# 01-CM4_Conn.net
KiCad netlist of a schematic drawn in Altium Designer
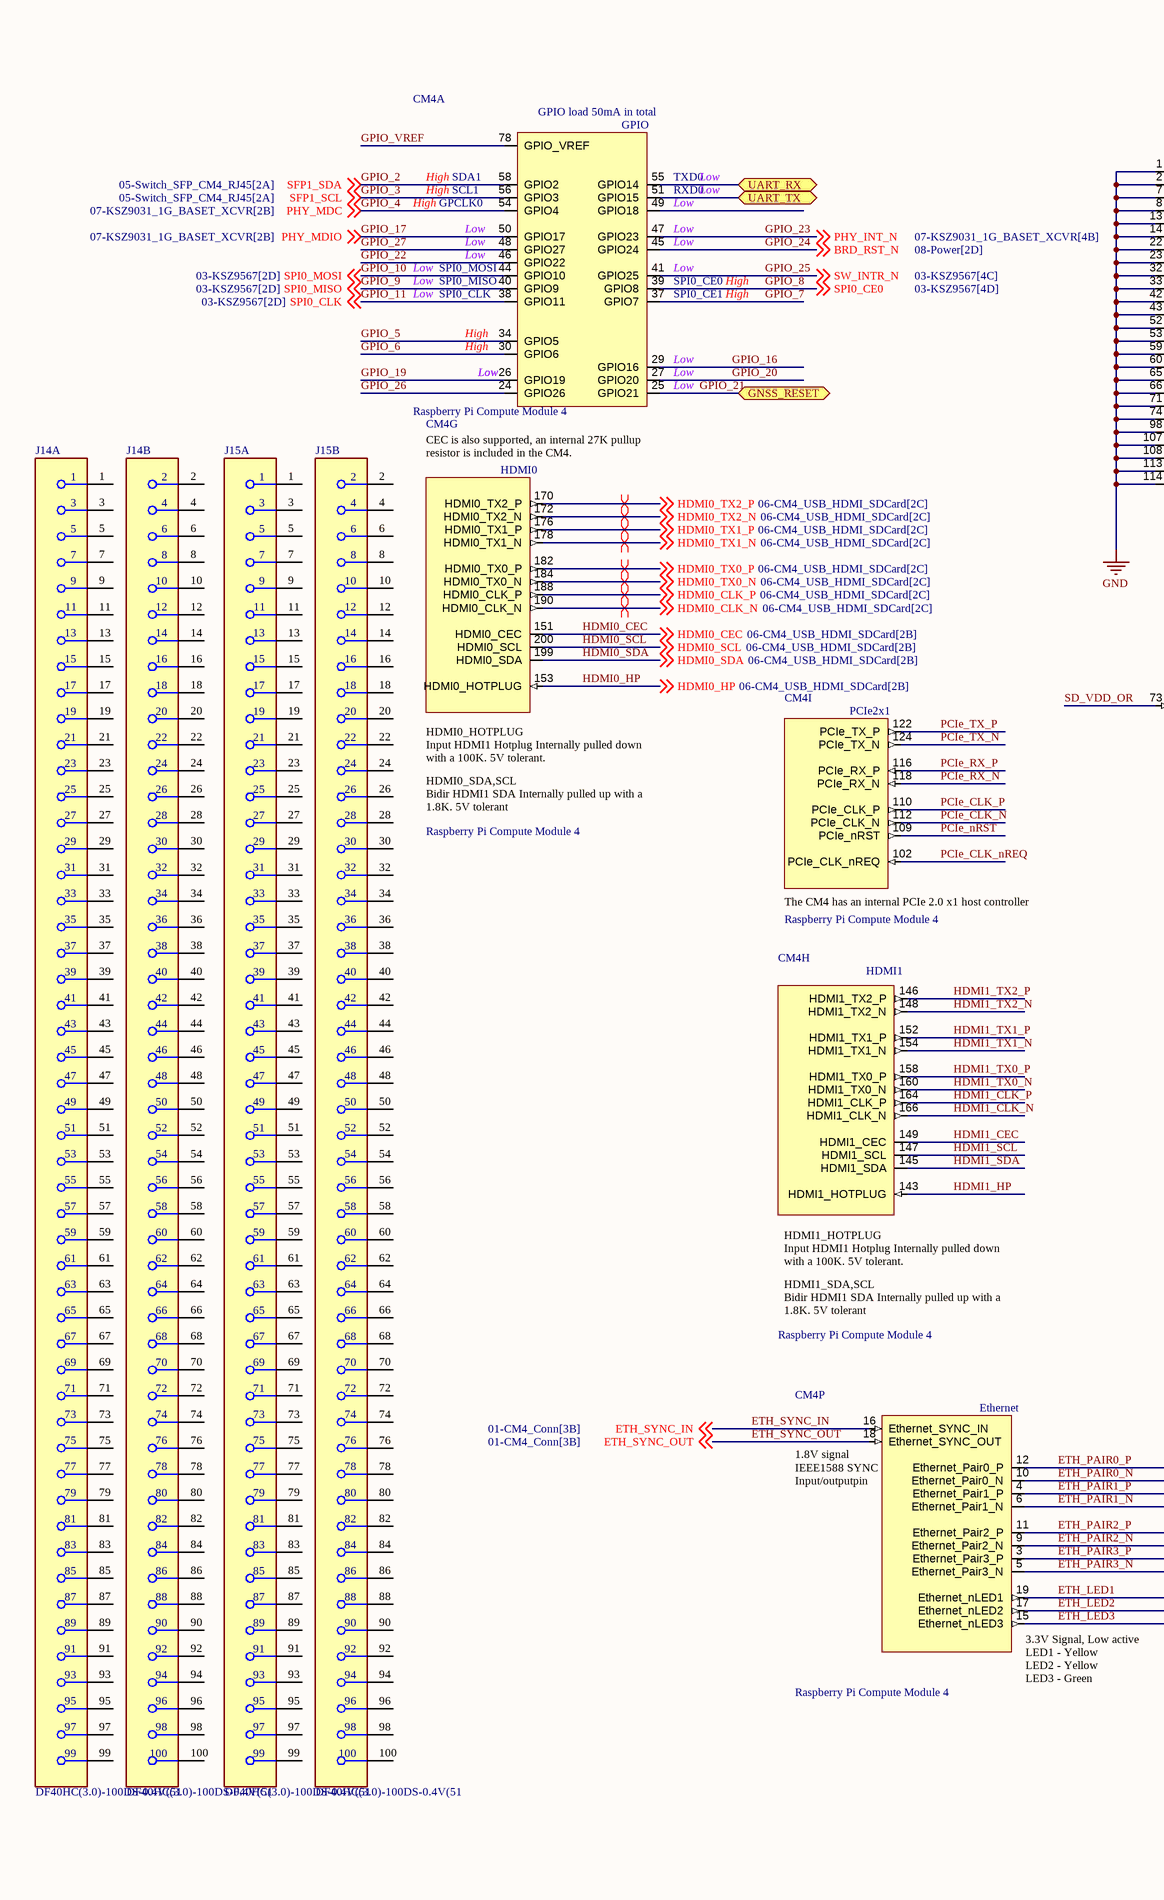
[diagram p0: 01-CM4_Conn.SchDoc, left]
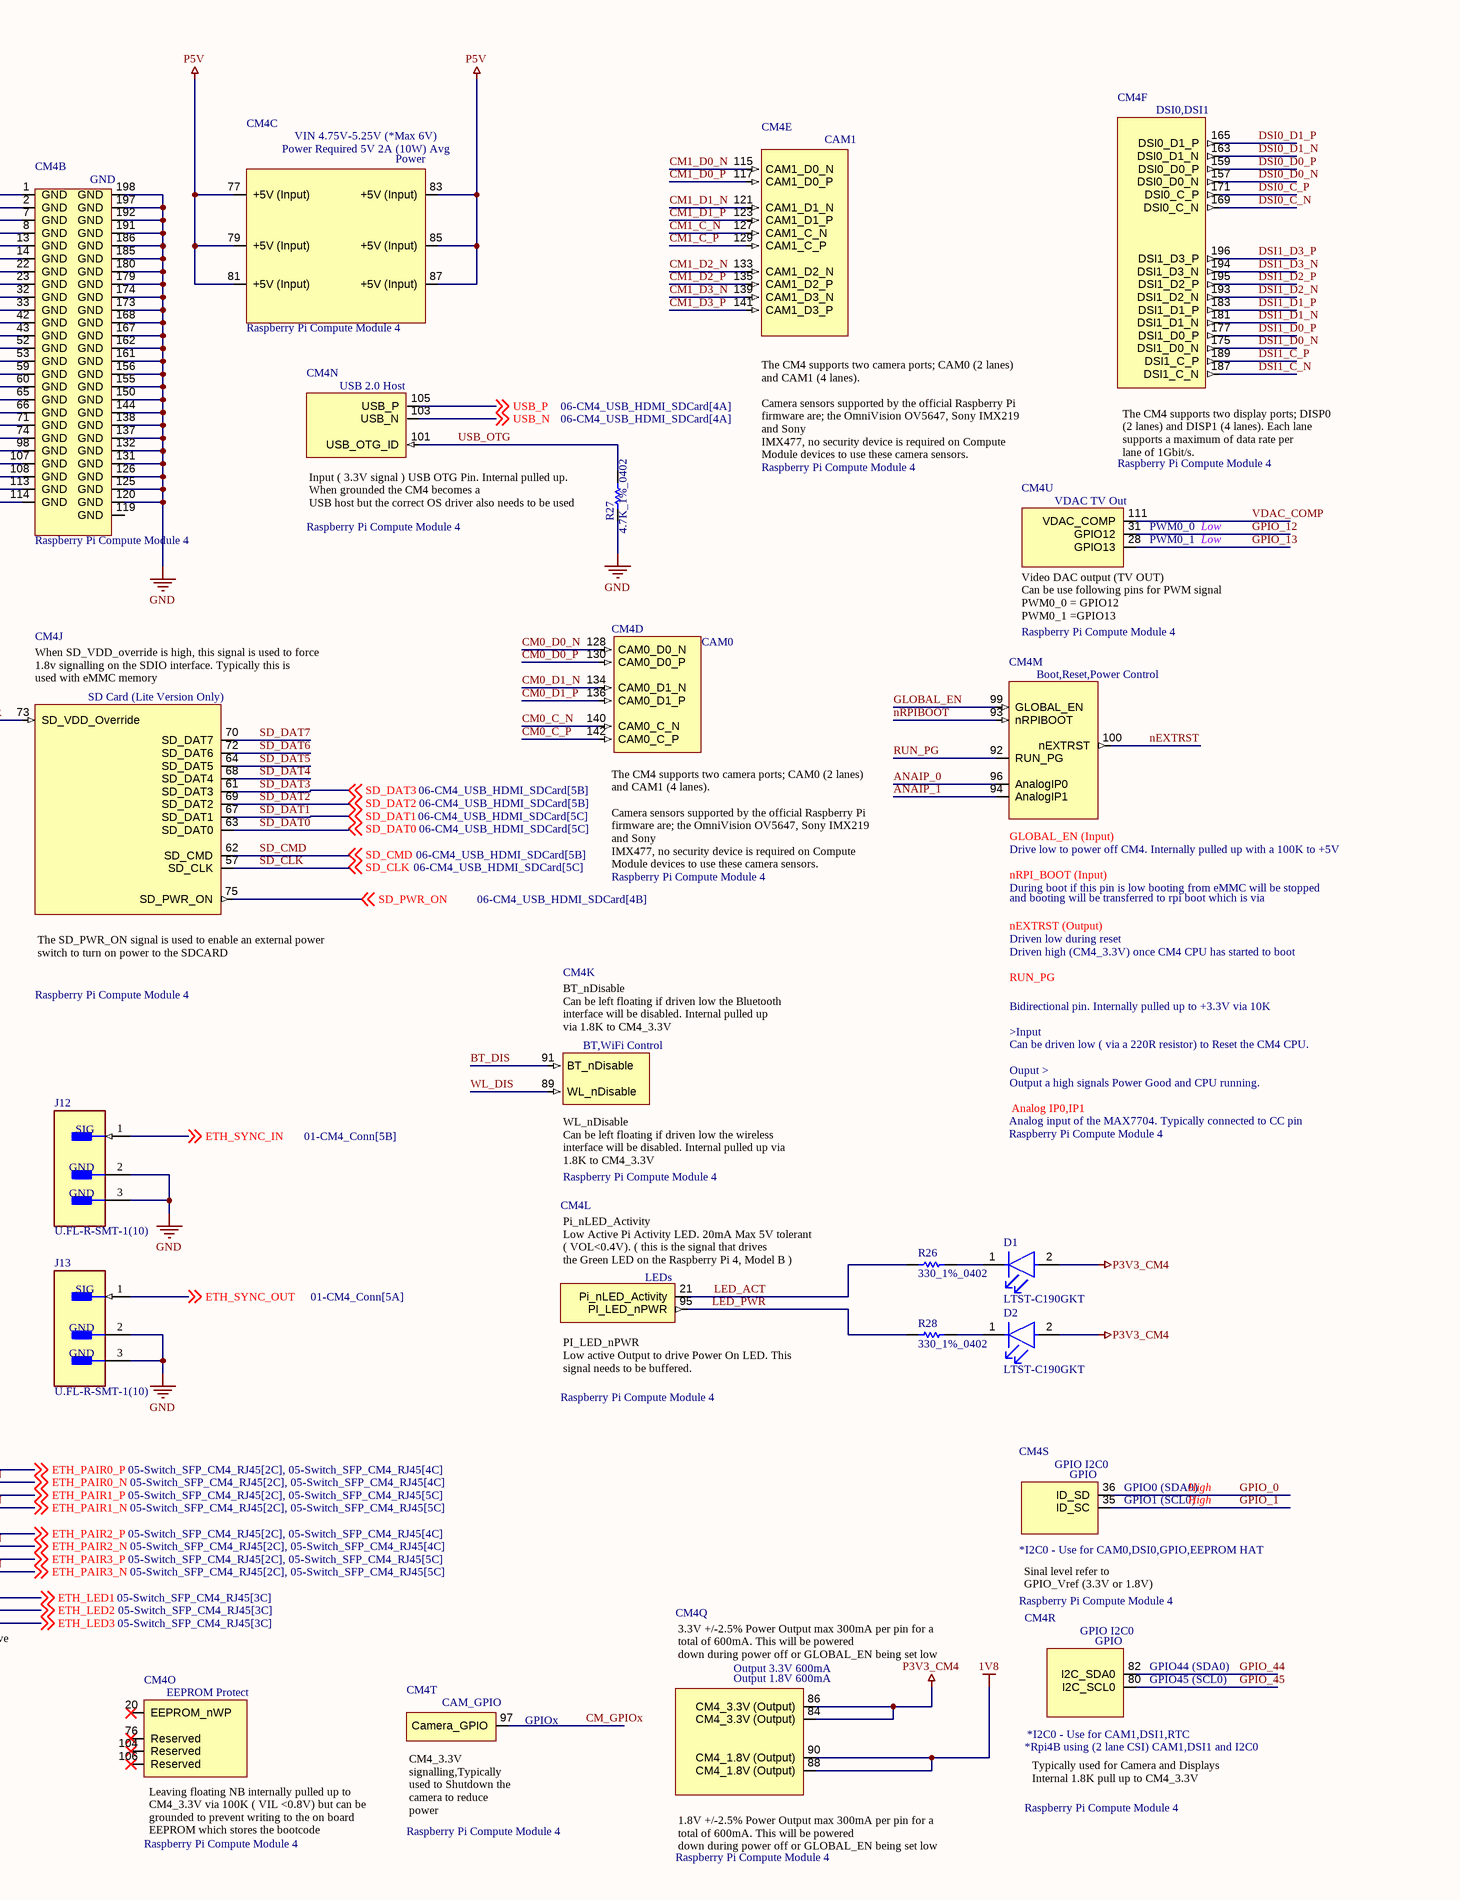
[diagram p1: 01-CM4_Conn.SchDoc, right]

(export (version "E")
  (design (tool "Eeschema 10.0.6"))
  (components
    (comp (ref "CM4")
      (value "Raspberry Pi Compute Module 4")
      (footprint "CM4-F40C-100DS-0.4v_1.5mm_0mm")
      (description "Raspberry Pi Compute Module 4 by Amornthep Phunsin")
      (libsource (lib "CM4") (part "CM4"))
    )
    (comp (ref "D1")
      (value "LTST-C190GKT")
      (footprint "FP-LTST-C190GKT-MFG")
      (description "LED GREEN CLEAR CHIP SMD")
      (fields (field (name "VOLTAGE") "2V"))
      (libsource (lib "Altium Content Vault") (part "8706943c75ba83719d021d2fdc84c58"))
    )
    (comp (ref "D2")
      (value "LTST-C190GKT")
      (footprint "FP-LTST-C190GKT-MFG")
      (description "LED GREEN CLEAR CHIP SMD")
      (fields (field (name "VOLTAGE") "2V"))
      (libsource (lib "Altium Content Vault") (part "8706943c75ba83719d021d2fdc84c58"))
    )
    (comp (ref "J12")
      (value "U.FL-R-SMT-1(10)")
      (footprint "FP-U_FL-R-SMT-1_10-MFG")
      (description "CONN U.FL RCPT STR 50 OHM SMD")
      (libsource (lib "Altium Content Vault") (part "7158abf7d987fa84906f6fb0d115710"))
    )
    (comp (ref "J13")
      (value "U.FL-R-SMT-1(10)")
      (footprint "FP-U_FL-R-SMT-1_10-MFG")
      (description "CONN U.FL RCPT STR 50 OHM SMD")
      (libsource (lib "Altium Content Vault") (part "7158abf7d987fa84906f6fb0d115710"))
    )
    (comp (ref "J14")
      (value "DF40HC(3.0)-100DS-0.4V(51")
      (footprint "FP-DF40HC_3_0_-100DS-0_4V-MFG")
      (description "CONN RCPT 100POS SMD GOLD")
      (libsource (lib "Altium Content Vault") (part "fa457dfecf3ebaea1b28843c89f182e"))
    )
    (comp (ref "J15")
      (value "DF40HC(3.0)-100DS-0.4V(51")
      (footprint "FP-DF40HC_3_0_-100DS-0_4V-MFG")
      (description "CONN RCPT 100POS SMD GOLD")
      (libsource (lib "Altium Content Vault") (part "fa457dfecf3ebaea1b28843c89f182e"))
    )
    (comp (ref "R26")
      (value "330_1%_0402")
      (footprint "RESC1005X40X25NL10T10")
      (fields (field (name "MANUFACTURER") "Panasonic") (field (name "PART NUMBER") "ERA-2AED331X"))
      (libsource (lib "Altium Content Vault") (part "RES"))
    )
    (comp (ref "R27")
      (value "4.7K_1%_0402")
      (footprint "RESC1005X40X25NL10T10")
      (fields (field (name "MANUFACTURER") "Bourns") (field (name "PART NUMBER") "CR0402-FX-4701GLF"))
      (libsource (lib "Altium Content Vault") (part "RES"))
    )
    (comp (ref "R28")
      (value "330_1%_0402")
      (footprint "RESC1005X40X25NL10T10")
      (fields (field (name "MANUFACTURER") "Panasonic") (field (name "PART NUMBER") "ERA-2AED331X"))
      (libsource (lib "Altium Content Vault") (part "RES"))
    )
  )
  (nets
    (net (code "1") (name "/ANAIP_0") (class "Default")
      (node (ref "CM4") (pin "96") (pinfunction "AnalogIP0_96") (pintype "passive"))
    )
    (net (code "2") (name "/ANAIP_1") (class "Default")
      (node (ref "CM4") (pin "94") (pinfunction "AnalogIP1_94") (pintype "passive"))
    )
    (net (code "3") (name "/BT_DIS") (class "Default")
      (node (ref "CM4") (pin "91") (pinfunction "BT_nDisable_91") (pintype "input"))
    )
    (net (code "4") (name "/CM0_C_N") (class "Default")
      (node (ref "CM4") (pin "140") (pinfunction "CAM0_C_N_140") (pintype "input"))
    )
    (net (code "5") (name "/CM0_C_P") (class "Default")
      (node (ref "CM4") (pin "142") (pinfunction "CAM0_C_P_142") (pintype "input"))
    )
    (net (code "6") (name "/CM0_D0_N") (class "Default")
      (node (ref "CM4") (pin "128") (pinfunction "CAM0_D0_N_128") (pintype "input"))
    )
    (net (code "7") (name "/CM0_D0_P") (class "Default")
      (node (ref "CM4") (pin "130") (pinfunction "CAM0_D0_P_130") (pintype "input"))
    )
    (net (code "8") (name "/CM0_D1_N") (class "Default")
      (node (ref "CM4") (pin "134") (pinfunction "CAM0_D1_N_134") (pintype "input"))
    )
    (net (code "9") (name "/CM0_D1_P") (class "Default")
      (node (ref "CM4") (pin "136") (pinfunction "CAM0_D1_P_136") (pintype "input"))
    )
    (net (code "10") (name "/CM1_C_N") (class "Default")
      (node (ref "CM4") (pin "127") (pinfunction "CAM1_C_N_127") (pintype "input"))
    )
    (net (code "11") (name "/CM1_C_P") (class "Default")
      (node (ref "CM4") (pin "129") (pinfunction "CAM1_C_P_129") (pintype "input"))
    )
    (net (code "12") (name "/CM1_D0_N") (class "Default")
      (node (ref "CM4") (pin "115") (pinfunction "CAM1_D0_N_115") (pintype "input"))
    )
    (net (code "13") (name "/CM1_D0_P") (class "Default")
      (node (ref "CM4") (pin "117") (pinfunction "CAM1_D0_P_117") (pintype "input"))
    )
    (net (code "14") (name "/CM1_D1_N") (class "Default")
      (node (ref "CM4") (pin "121") (pinfunction "CAM1_D1_N_121") (pintype "input"))
    )
    (net (code "15") (name "/CM1_D1_P") (class "Default")
      (node (ref "CM4") (pin "123") (pinfunction "CAM1_D1_P_123") (pintype "input"))
    )
    (net (code "16") (name "/CM1_D2_N") (class "Default")
      (node (ref "CM4") (pin "133") (pinfunction "CAM1_D2_N_133") (pintype "input"))
    )
    (net (code "17") (name "/CM1_D2_P") (class "Default")
      (node (ref "CM4") (pin "135") (pinfunction "CAM1_D2_P_135") (pintype "input"))
    )
    (net (code "18") (name "/CM1_D3_N") (class "Default")
      (node (ref "CM4") (pin "139") (pinfunction "CAM1_D3_N_139") (pintype "input"))
    )
    (net (code "19") (name "/CM1_D3_P") (class "Default")
      (node (ref "CM4") (pin "141") (pinfunction "CAM1_D3_P_141") (pintype "input"))
    )
    (net (code "20") (name "/CM_GPIOx") (class "Default")
      (node (ref "CM4") (pin "97") (pinfunction "Camera_GPIO_97") (pintype "passive"))
    )
    (net (code "21") (name "/DSI0_C_N") (class "Default")
      (node (ref "CM4") (pin "169") (pinfunction "DSI0_C_N_169") (pintype "output"))
    )
    (net (code "22") (name "/DSI0_C_P") (class "Default")
      (node (ref "CM4") (pin "171") (pinfunction "DSI0_C_P_171") (pintype "output"))
    )
    (net (code "23") (name "/DSI0_D0_N") (class "Default")
      (node (ref "CM4") (pin "157") (pinfunction "DSI0_D0_N_157") (pintype "output"))
    )
    (net (code "24") (name "/DSI0_D0_P") (class "Default")
      (node (ref "CM4") (pin "159") (pinfunction "DSI0_D0_P_159") (pintype "output"))
    )
    (net (code "25") (name "/DSI0_D1_N") (class "Default")
      (node (ref "CM4") (pin "163") (pinfunction "DSI0_D1_N_163") (pintype "output"))
    )
    (net (code "26") (name "/DSI0_D1_P") (class "Default")
      (node (ref "CM4") (pin "165") (pinfunction "DSI0_D1_P_165") (pintype "output"))
    )
    (net (code "27") (name "/DSI1_C_N") (class "Default")
      (node (ref "CM4") (pin "187") (pinfunction "DSI1_C_N_187") (pintype "output"))
    )
    (net (code "28") (name "/DSI1_C_P") (class "Default")
      (node (ref "CM4") (pin "189") (pinfunction "DSI1_C_P_189") (pintype "output"))
    )
    (net (code "29") (name "/DSI1_D0_N") (class "Default")
      (node (ref "CM4") (pin "175") (pinfunction "DSI1_D0_N_175") (pintype "output"))
    )
    (net (code "30") (name "/DSI1_D0_P") (class "Default")
      (node (ref "CM4") (pin "177") (pinfunction "DSI1_D0_P_177") (pintype "output"))
    )
    (net (code "31") (name "/DSI1_D1_N") (class "Default")
      (node (ref "CM4") (pin "181") (pinfunction "DSI1_D1_N_181") (pintype "output"))
    )
    (net (code "32") (name "/DSI1_D1_P") (class "Default")
      (node (ref "CM4") (pin "183") (pinfunction "DSI1_D1_P_183") (pintype "output"))
    )
    (net (code "33") (name "/DSI1_D2_N") (class "Default")
      (node (ref "CM4") (pin "193") (pinfunction "DSI1_D2_N_193") (pintype "output"))
    )
    (net (code "34") (name "/DSI1_D2_P") (class "Default")
      (node (ref "CM4") (pin "195") (pinfunction "DSI1_D2_P_195") (pintype "output"))
    )
    (net (code "35") (name "/DSI1_D3_N") (class "Default")
      (node (ref "CM4") (pin "194") (pinfunction "DSI1_D3_N_194") (pintype "output"))
    )
    (net (code "36") (name "/DSI1_D3_P") (class "Default")
      (node (ref "CM4") (pin "196") (pinfunction "DSI1_D3_P_196") (pintype "output"))
    )
    (net (code "37") (name "/GLOBAL_EN") (class "Default")
      (node (ref "CM4") (pin "99") (pinfunction "GLOBAL_EN_99") (pintype "input"))
    )
    (net (code "38") (name "/GPIO_0") (class "Default")
      (node (ref "CM4") (pin "36") (pinfunction "ID_SD_36") (pintype "passive"))
    )
    (net (code "39") (name "/GPIO_1") (class "Default")
      (node (ref "CM4") (pin "35") (pinfunction "ID_SC_35") (pintype "passive"))
    )
    (net (code "40") (name "/GPIO_5") (class "Default")
      (node (ref "CM4") (pin "34") (pinfunction "GPIO5_34") (pintype "passive"))
    )
    (net (code "41") (name "/GPIO_6") (class "Default")
      (node (ref "CM4") (pin "30") (pinfunction "GPIO6_30") (pintype "passive"))
    )
    (net (code "42") (name "/GPIO_7") (class "Default")
      (node (ref "CM4") (pin "37") (pinfunction "GPIO7_37") (pintype "passive"))
    )
    (net (code "43") (name "/GPIO_12") (class "Default")
      (node (ref "CM4") (pin "31") (pinfunction "GPIO12_31") (pintype "passive"))
    )
    (net (code "44") (name "/GPIO_13") (class "Default")
      (node (ref "CM4") (pin "28") (pinfunction "GPIO13_28") (pintype "passive"))
    )
    (net (code "45") (name "/GPIO_16") (class "Default")
      (node (ref "CM4") (pin "29") (pinfunction "GPIO16_29") (pintype "passive"))
    )
    (net (code "46") (name "/GPIO_19") (class "Default")
      (node (ref "CM4") (pin "26") (pinfunction "GPIO19_26") (pintype "passive"))
    )
    (net (code "47") (name "/GPIO_20") (class "Default")
      (node (ref "CM4") (pin "27") (pinfunction "GPIO20_27") (pintype "passive"))
    )
    (net (code "48") (name "/GPIO_21") (class "Default")
      (node (ref "CM4") (pin "25") (pinfunction "GPIO21_25") (pintype "passive"))
    )
    (net (code "49") (name "/GPIO_22") (class "Default")
      (node (ref "CM4") (pin "46") (pinfunction "GPIO22_46") (pintype "passive"))
    )
    (net (code "50") (name "/GPIO_26") (class "Default")
      (node (ref "CM4") (pin "24") (pinfunction "GPIO26_24") (pintype "passive"))
    )
    (net (code "51") (name "/GPIO_27") (class "Default")
      (node (ref "CM4") (pin "48") (pinfunction "GPIO27_48") (pintype "passive"))
    )
    (net (code "52") (name "/GPIO_44") (class "Default")
      (node (ref "CM4") (pin "82") (pinfunction "I2C_SDA0_82") (pintype "passive"))
    )
    (net (code "53") (name "/GPIO_45") (class "Default")
      (node (ref "CM4") (pin "80") (pinfunction "I2C_SCL0_80") (pintype "passive"))
    )
    (net (code "54") (name "/GPIO_VREF") (class "Default")
      (node (ref "CM4") (pin "78") (pinfunction "GPIO_VREF_78") (pintype "power_in"))
    )
    (net (code "55") (name "/HDMI1_CEC") (class "Default")
      (node (ref "CM4") (pin "149") (pinfunction "HDMI1_CEC_149") (pintype "open_collector"))
    )
    (net (code "56") (name "/HDMI1_CLK_N") (class "Default")
      (node (ref "CM4") (pin "166") (pinfunction "HDMI1_CLK_N_166") (pintype "output"))
    )
    (net (code "57") (name "/HDMI1_CLK_P") (class "Default")
      (node (ref "CM4") (pin "164") (pinfunction "HDMI1_CLK_P_164") (pintype "output"))
    )
    (net (code "58") (name "/HDMI1_HP") (class "Default")
      (node (ref "CM4") (pin "143") (pinfunction "HDMI1_HOTPLUG_143") (pintype "input"))
    )
    (net (code "59") (name "/HDMI1_SCL") (class "Default")
      (node (ref "CM4") (pin "147") (pinfunction "HDMI1_SCL_147") (pintype "open_collector"))
    )
    (net (code "60") (name "/HDMI1_SDA") (class "Default")
      (node (ref "CM4") (pin "145") (pinfunction "HDMI1_SDA_145") (pintype "bidirectional"))
    )
    (net (code "61") (name "/HDMI1_TX0_N") (class "Default")
      (node (ref "CM4") (pin "160") (pinfunction "HDMI1_TX0_N_160") (pintype "output"))
    )
    (net (code "62") (name "/HDMI1_TX0_P") (class "Default")
      (node (ref "CM4") (pin "158") (pinfunction "HDMI1_TX0_P_158") (pintype "output"))
    )
    (net (code "63") (name "/HDMI1_TX1_N") (class "Default")
      (node (ref "CM4") (pin "154") (pinfunction "HDMI1_TX1_N_154") (pintype "output"))
    )
    (net (code "64") (name "/HDMI1_TX1_P") (class "Default")
      (node (ref "CM4") (pin "152") (pinfunction "HDMI1_TX1_P_152") (pintype "output"))
    )
    (net (code "65") (name "/HDMI1_TX2_N") (class "Default")
      (node (ref "CM4") (pin "148") (pinfunction "HDMI1_TX2_N_148") (pintype "output"))
    )
    (net (code "66") (name "/HDMI1_TX2_P") (class "Default")
      (node (ref "CM4") (pin "146") (pinfunction "HDMI1_TX2_P_146") (pintype "output"))
    )
    (net (code "67") (name "/LED_ACT") (class "Default")
      (node (ref "CM4") (pin "21") (pinfunction "Pi_nLED_Activity_21") (pintype "open_collector"))
      (node (ref "R26") (pin "1") (pinfunction "1_1") (pintype "passive"))
    )
    (net (code "68") (name "/LED_PWR") (class "Default")
      (node (ref "CM4") (pin "95") (pinfunction "PI_LED_nPWR_95") (pintype "output"))
      (node (ref "R28") (pin "1") (pinfunction "1_1") (pintype "passive"))
    )
    (net (code "69") (name "/PCIe_CLK_N") (class "Default")
      (node (ref "CM4") (pin "112") (pinfunction "PCIe_CLK_N_112") (pintype "output"))
    )
    (net (code "70") (name "/PCIe_CLK_P") (class "Default")
      (node (ref "CM4") (pin "110") (pinfunction "PCIe_CLK_P_110") (pintype "output"))
    )
    (net (code "71") (name "/PCIe_CLK_nREQ") (class "Default")
      (node (ref "CM4") (pin "102") (pinfunction "PCIe_CLK_nREQ_102") (pintype "input"))
    )
    (net (code "72") (name "/PCIe_RX_N") (class "Default")
      (node (ref "CM4") (pin "118") (pinfunction "PCIe_RX_N_118") (pintype "input"))
    )
    (net (code "73") (name "/PCIe_RX_P") (class "Default")
      (node (ref "CM4") (pin "116") (pinfunction "PCIe_RX_P_116") (pintype "input"))
    )
    (net (code "74") (name "/PCIe_TX_N") (class "Default")
      (node (ref "CM4") (pin "124") (pinfunction "PCIe_TX_N_124") (pintype "output"))
    )
    (net (code "75") (name "/PCIe_TX_P") (class "Default")
      (node (ref "CM4") (pin "122") (pinfunction "PCIe_TX_P_122") (pintype "output"))
    )
    (net (code "76") (name "/PCIe_nRST") (class "Default")
      (node (ref "CM4") (pin "109") (pinfunction "PCIe_nRST_109") (pintype "output"))
    )
    (net (code "77") (name "/RUN_PG") (class "Default")
      (node (ref "CM4") (pin "92") (pinfunction "RUN_PG_92") (pintype "passive"))
    )
    (net (code "78") (name "/SD_DAT4") (class "Default")
      (node (ref "CM4") (pin "68") (pinfunction "SD_DAT4_68") (pintype "passive"))
    )
    (net (code "79") (name "/SD_DAT5") (class "Default")
      (node (ref "CM4") (pin "64") (pinfunction "SD_DAT5_64") (pintype "passive"))
    )
    (net (code "80") (name "/SD_DAT6") (class "Default")
      (node (ref "CM4") (pin "72") (pinfunction "SD_DAT6_72") (pintype "passive"))
    )
    (net (code "81") (name "/SD_DAT7") (class "Default")
      (node (ref "CM4") (pin "70") (pinfunction "SD_DAT7_70") (pintype "passive"))
    )
    (net (code "82") (name "/SD_VDD_OR") (class "Default")
      (node (ref "CM4") (pin "73") (pinfunction "SD_VDD_Override_73") (pintype "input"))
    )
    (net (code "83") (name "/UART_RX") (class "Default")
      (node (ref "CM4") (pin "55") (pinfunction "GPIO14_55") (pintype "passive"))
    )
    (net (code "84") (name "/UART_TX") (class "Default")
      (node (ref "CM4") (pin "51") (pinfunction "GPIO15_51") (pintype "passive"))
    )
    (net (code "85") (name "/USB_OTG") (class "Default")
      (node (ref "CM4") (pin "101") (pinfunction "USB_OTG_ID_101") (pintype "input"))
      (node (ref "R27") (pin "1") (pinfunction "1_1") (pintype "passive"))
    )
    (net (code "86") (name "/VDAC_COMP") (class "Default")
      (node (ref "CM4") (pin "111") (pinfunction "VDAC_COMP_111") (pintype "passive"))
    )
    (net (code "87") (name "/WL_DIS") (class "Default")
      (node (ref "CM4") (pin "89") (pinfunction "WL_nDisable_89") (pintype "input"))
    )
    (net (code "88") (name "/nEXTRST") (class "Default")
      (node (ref "CM4") (pin "100") (pinfunction "nEXTRST_100") (pintype "output"))
    )
    (net (code "89") (name "/nRPIBOOT") (class "Default")
      (node (ref "CM4") (pin "93") (pinfunction "nRPIBOOT_93") (pintype "input"))
    )
    (net (code "90") (name "1V8") (class "Default")
      (node (ref "CM4") (pin "88") (pinfunction "CM4_1.8V_(Output)_88") (pintype "power_in"))
      (node (ref "CM4") (pin "90") (pinfunction "CM4_1.8V_(Output)_90") (pintype "power_in"))
    )
    (net (code "91") (name "BRD_RST_N") (class "Default")
      (node (ref "CM4") (pin "45") (pinfunction "GPIO24_45") (pintype "passive"))
    )
    (net (code "92") (name "ETH_LED1") (class "Default")
      (node (ref "CM4") (pin "19") (pinfunction "Ethernet_nLED1_19") (pintype "output"))
    )
    (net (code "93") (name "ETH_LED2") (class "Default")
      (node (ref "CM4") (pin "17") (pinfunction "Ethernet_nLED2_17") (pintype "output"))
    )
    (net (code "94") (name "ETH_LED3") (class "Default")
      (node (ref "CM4") (pin "15") (pinfunction "Ethernet_nLED3_15") (pintype "output"))
    )
    (net (code "95") (name "ETH_PAIR0_N") (class "Default")
      (node (ref "CM4") (pin "10") (pinfunction "Ethernet_Pair0_N_10") (pintype "passive"))
    )
    (net (code "96") (name "ETH_PAIR0_P") (class "Default")
      (node (ref "CM4") (pin "12") (pinfunction "Ethernet_Pair0_P_12") (pintype "passive"))
    )
    (net (code "97") (name "ETH_PAIR1_N") (class "Default")
      (node (ref "CM4") (pin "6") (pinfunction "Ethernet_Pair1_N_6") (pintype "passive"))
    )
    (net (code "98") (name "ETH_PAIR1_P") (class "Default")
      (node (ref "CM4") (pin "4") (pinfunction "Ethernet_Pair1_P_4") (pintype "passive"))
    )
    (net (code "99") (name "ETH_PAIR2_N") (class "Default")
      (node (ref "CM4") (pin "9") (pinfunction "Ethernet_Pair2_N_9") (pintype "passive"))
    )
    (net (code "100") (name "ETH_PAIR2_P") (class "Default")
      (node (ref "CM4") (pin "11") (pinfunction "Ethernet_Pair2_P_11") (pintype "passive"))
    )
    (net (code "101") (name "ETH_PAIR3_N") (class "Default")
      (node (ref "CM4") (pin "5") (pinfunction "Ethernet_Pair3_N_5") (pintype "passive"))
    )
    (net (code "102") (name "ETH_PAIR3_P") (class "Default")
      (node (ref "CM4") (pin "3") (pinfunction "Ethernet_Pair3_P_3") (pintype "passive"))
    )
    (net (code "103") (name "ETH_SYNC_IN") (class "Default")
      (node (ref "CM4") (pin "16") (pinfunction "Ethernet_SYNC_IN_16") (pintype "input"))
      (node (ref "J12") (pin "1") (pinfunction "SIG_1") (pintype "input"))
    )
    (net (code "104") (name "ETH_SYNC_OUT") (class "Default")
      (node (ref "CM4") (pin "18") (pinfunction "Ethernet_SYNC_OUT_18") (pintype "input"))
      (node (ref "J13") (pin "1") (pinfunction "SIG_1") (pintype "input"))
    )
    (net (code "105") (name "GND") (class "Default")
      (node (ref "CM4") (pin "1") (pinfunction "GND_1") (pintype "power_in"))
      (node (ref "CM4") (pin "107") (pinfunction "GND_107") (pintype "power_in"))
      (node (ref "CM4") (pin "108") (pinfunction "GND_108") (pintype "power_in"))
      (node (ref "CM4") (pin "113") (pinfunction "GND_113") (pintype "power_in"))
      (node (ref "CM4") (pin "114") (pinfunction "GND_114") (pintype "power_in"))
      (node (ref "CM4") (pin "120") (pinfunction "GND_120") (pintype "power_in"))
      (node (ref "CM4") (pin "125") (pinfunction "GND_125") (pintype "power_in"))
      (node (ref "CM4") (pin "126") (pinfunction "GND_126") (pintype "power_in"))
      (node (ref "CM4") (pin "13") (pinfunction "GND_13") (pintype "power_in"))
      (node (ref "CM4") (pin "131") (pinfunction "GND_131") (pintype "power_in"))
      (node (ref "CM4") (pin "132") (pinfunction "GND_132") (pintype "power_in"))
      (node (ref "CM4") (pin "137") (pinfunction "GND_137") (pintype "power_in"))
      (node (ref "CM4") (pin "138") (pinfunction "GND_138") (pintype "power_in"))
      (node (ref "CM4") (pin "14") (pinfunction "GND_14") (pintype "power_in"))
      (node (ref "CM4") (pin "144") (pinfunction "GND_144") (pintype "power_in"))
      (node (ref "CM4") (pin "150") (pinfunction "GND_150") (pintype "power_in"))
      (node (ref "CM4") (pin "155") (pinfunction "GND_155") (pintype "power_in"))
      (node (ref "CM4") (pin "156") (pinfunction "GND_156") (pintype "power_in"))
      (node (ref "CM4") (pin "161") (pinfunction "GND_161") (pintype "power_in"))
      (node (ref "CM4") (pin "162") (pinfunction "GND_162") (pintype "power_in"))
      (node (ref "CM4") (pin "167") (pinfunction "GND_167") (pintype "power_in"))
      (node (ref "CM4") (pin "168") (pinfunction "GND_168") (pintype "power_in"))
      (node (ref "CM4") (pin "173") (pinfunction "GND_173") (pintype "power_in"))
      (node (ref "CM4") (pin "174") (pinfunction "GND_174") (pintype "power_in"))
      (node (ref "CM4") (pin "179") (pinfunction "GND_179") (pintype "power_in"))
      (node (ref "CM4") (pin "180") (pinfunction "GND_180") (pintype "power_in"))
      (node (ref "CM4") (pin "185") (pinfunction "GND_185") (pintype "power_in"))
      (node (ref "CM4") (pin "186") (pinfunction "GND_186") (pintype "power_in"))
      (node (ref "CM4") (pin "191") (pinfunction "GND_191") (pintype "power_in"))
      (node (ref "CM4") (pin "192") (pinfunction "GND_192") (pintype "power_in"))
      (node (ref "CM4") (pin "197") (pinfunction "GND_197") (pintype "power_in"))
      (node (ref "CM4") (pin "198") (pinfunction "GND_198") (pintype "power_in"))
      (node (ref "CM4") (pin "2") (pinfunction "GND_2") (pintype "power_in"))
      (node (ref "CM4") (pin "22") (pinfunction "GND_22") (pintype "power_in"))
      (node (ref "CM4") (pin "23") (pinfunction "GND_23") (pintype "power_in"))
      (node (ref "CM4") (pin "32") (pinfunction "GND_32") (pintype "power_in"))
      (node (ref "CM4") (pin "33") (pinfunction "GND_33") (pintype "power_in"))
      (node (ref "CM4") (pin "42") (pinfunction "GND_42") (pintype "power_in"))
      (node (ref "CM4") (pin "43") (pinfunction "GND_43") (pintype "power_in"))
      (node (ref "CM4") (pin "52") (pinfunction "GND_52") (pintype "power_in"))
      (node (ref "CM4") (pin "53") (pinfunction "GND_53") (pintype "power_in"))
      (node (ref "CM4") (pin "59") (pinfunction "GND_59") (pintype "power_in"))
      (node (ref "CM4") (pin "60") (pinfunction "GND_60") (pintype "power_in"))
      (node (ref "CM4") (pin "65") (pinfunction "GND_65") (pintype "power_in"))
      (node (ref "CM4") (pin "66") (pinfunction "GND_66") (pintype "power_in"))
      (node (ref "CM4") (pin "7") (pinfunction "GND_7") (pintype "power_in"))
      (node (ref "CM4") (pin "71") (pinfunction "GND_71") (pintype "power_in"))
      (node (ref "CM4") (pin "74") (pinfunction "GND_74") (pintype "power_in"))
      (node (ref "CM4") (pin "8") (pinfunction "GND_8") (pintype "power_in"))
      (node (ref "CM4") (pin "98") (pinfunction "GND_98") (pintype "power_in"))
      (node (ref "J12") (pin "2") (pinfunction "GND_2") (pintype "power_in"))
      (node (ref "J12") (pin "3") (pinfunction "GND_3") (pintype "power_in"))
      (node (ref "J13") (pin "2") (pinfunction "GND_2") (pintype "power_in"))
      (node (ref "J13") (pin "3") (pinfunction "GND_3") (pintype "power_in"))
      (node (ref "R27") (pin "2") (pinfunction "2_2") (pintype "passive"))
    )
    (net (code "106") (name "HDMI0_CEC") (class "Default")
      (node (ref "CM4") (pin "151") (pinfunction "HDMI0_CEC_151") (pintype "open_collector"))
    )
    (net (code "107") (name "HDMI0_CLK_N") (class "Default")
      (node (ref "CM4") (pin "190") (pinfunction "HDMI0_CLK_N_190") (pintype "output"))
    )
    (net (code "108") (name "HDMI0_CLK_P") (class "Default")
      (node (ref "CM4") (pin "188") (pinfunction "HDMI0_CLK_P_188") (pintype "output"))
    )
    (net (code "109") (name "HDMI0_HP") (class "Default")
      (node (ref "CM4") (pin "153") (pinfunction "HDMI0_HOTPLUG_153") (pintype "input"))
    )
    (net (code "110") (name "HDMI0_SCL") (class "Default")
      (node (ref "CM4") (pin "200") (pinfunction "HDMI0_SCL_200") (pintype "open_collector"))
    )
    (net (code "111") (name "HDMI0_SDA") (class "Default")
      (node (ref "CM4") (pin "199") (pinfunction "HDMI0_SDA_199") (pintype "bidirectional"))
    )
    (net (code "112") (name "HDMI0_TX0_N") (class "Default")
      (node (ref "CM4") (pin "184") (pinfunction "HDMI0_TX0_N_184") (pintype "output"))
    )
    (net (code "113") (name "HDMI0_TX0_P") (class "Default")
      (node (ref "CM4") (pin "182") (pinfunction "HDMI0_TX0_P_182") (pintype "output"))
    )
    (net (code "114") (name "HDMI0_TX1_N") (class "Default")
      (node (ref "CM4") (pin "178") (pinfunction "HDMI0_TX1_N_178") (pintype "output"))
    )
    (net (code "115") (name "HDMI0_TX1_P") (class "Default")
      (node (ref "CM4") (pin "176") (pinfunction "HDMI0_TX1_P_176") (pintype "output"))
    )
    (net (code "116") (name "HDMI0_TX2_N") (class "Default")
      (node (ref "CM4") (pin "172") (pinfunction "HDMI0_TX2_N_172") (pintype "output"))
    )
    (net (code "117") (name "HDMI0_TX2_P") (class "Default")
      (node (ref "CM4") (pin "170") (pinfunction "HDMI0_TX2_P_170") (pintype "output"))
    )
    (net (code "118") (name "Net-(D1-C)") (class "Default")
      (node (ref "D1") (pin "1") (pinfunction "C_1") (pintype "passive"))
      (node (ref "R26") (pin "2") (pinfunction "2_2") (pintype "passive"))
    )
    (net (code "119") (name "Net-(D2-C)") (class "Default")
      (node (ref "D2") (pin "1") (pinfunction "C_1") (pintype "passive"))
      (node (ref "R28") (pin "2") (pinfunction "2_2") (pintype "passive"))
    )
    (net (code "120") (name "P3V3_CM4") (class "Default")
      (node (ref "CM4") (pin "84") (pinfunction "CM4_3.3V_(Output)_84") (pintype "power_in"))
      (node (ref "CM4") (pin "86") (pinfunction "CM4_3.3V_(Output)_86") (pintype "power_in"))
      (node (ref "D1") (pin "2") (pinfunction "A_2") (pintype "passive"))
      (node (ref "D2") (pin "2") (pinfunction "A_2") (pintype "passive"))
    )
    (net (code "121") (name "P5V") (class "Default")
      (node (ref "CM4") (pin "77") (pinfunction "+5V_(Input)_77") (pintype "power_in"))
      (node (ref "CM4") (pin "79") (pinfunction "+5V_(Input)_79") (pintype "power_in"))
      (node (ref "CM4") (pin "81") (pinfunction "+5V_(Input)_81") (pintype "power_in"))
      (node (ref "CM4") (pin "83") (pinfunction "+5V_(Input)_83") (pintype "power_in"))
      (node (ref "CM4") (pin "85") (pinfunction "+5V_(Input)_85") (pintype "power_in"))
      (node (ref "CM4") (pin "87") (pinfunction "+5V_(Input)_87") (pintype "power_in"))
    )
    (net (code "122") (name "PHY_INT_N") (class "Default")
      (node (ref "CM4") (pin "47") (pinfunction "GPIO23_47") (pintype "passive"))
    )
    (net (code "123") (name "PHY_MDC") (class "Default")
      (node (ref "CM4") (pin "54") (pinfunction "GPIO4_54") (pintype "passive"))
    )
    (net (code "124") (name "PHY_MDIO") (class "Default")
      (node (ref "CM4") (pin "50") (pinfunction "GPIO17_50") (pintype "passive"))
    )
    (net (code "125") (name "SD_CLK") (class "Default")
      (node (ref "CM4") (pin "57") (pinfunction "SD_CLK_57") (pintype "passive"))
    )
    (net (code "126") (name "SD_CMD") (class "Default")
      (node (ref "CM4") (pin "62") (pinfunction "SD_CMD_62") (pintype "passive"))
    )
    (net (code "127") (name "SD_DAT0") (class "Default")
      (node (ref "CM4") (pin "63") (pinfunction "SD_DAT0_63") (pintype "passive"))
    )
    (net (code "128") (name "SD_DAT1") (class "Default")
      (node (ref "CM4") (pin "67") (pinfunction "SD_DAT1_67") (pintype "passive"))
    )
    (net (code "129") (name "SD_DAT2") (class "Default")
      (node (ref "CM4") (pin "69") (pinfunction "SD_DAT2_69") (pintype "passive"))
    )
    (net (code "130") (name "SD_DAT3") (class "Default")
      (node (ref "CM4") (pin "61") (pinfunction "SD_DAT3_61") (pintype "passive"))
    )
    (net (code "131") (name "SD_PWR_ON") (class "Default")
      (node (ref "CM4") (pin "75") (pinfunction "SD_PWR_ON_75") (pintype "output"))
    )
    (net (code "132") (name "SFP1_SCL") (class "Default")
      (node (ref "CM4") (pin "56") (pinfunction "GPIO3_56") (pintype "passive"))
    )
    (net (code "133") (name "SFP1_SDA") (class "Default")
      (node (ref "CM4") (pin "58") (pinfunction "GPIO2_58") (pintype "passive"))
    )
    (net (code "134") (name "SPI0_CE0") (class "Default")
      (node (ref "CM4") (pin "39") (pinfunction "GPIO8_39") (pintype "passive"))
    )
    (net (code "135") (name "SPI0_CLK") (class "Default")
      (node (ref "CM4") (pin "38") (pinfunction "GPIO11_38") (pintype "passive"))
    )
    (net (code "136") (name "SPI0_MISO") (class "Default")
      (node (ref "CM4") (pin "40") (pinfunction "GPIO9_40") (pintype "passive"))
    )
    (net (code "137") (name "SPI0_MOSI") (class "Default")
      (node (ref "CM4") (pin "44") (pinfunction "GPIO10_44") (pintype "passive"))
    )
    (net (code "138") (name "SW_INTR_N") (class "Default")
      (node (ref "CM4") (pin "41") (pinfunction "GPIO25_41") (pintype "passive"))
    )
    (net (code "139") (name "USB_N") (class "Default")
      (node (ref "CM4") (pin "103") (pinfunction "USB_N_103") (pintype "passive"))
    )
    (net (code "140") (name "USB_P") (class "Default")
      (node (ref "CM4") (pin "105") (pinfunction "USB_P_105") (pintype "passive"))
    )
    (net (code "141") (name "unconnected-(CM4A-GPIO18-Pad49)") (class "Default")
      (node (ref "CM4") (pin "49") (pinfunction "GPIO18_49") (pintype "passive"))
    )
    (net (code "142") (name "unconnected-(CM4B-GND-Pad119)") (class "Default")
      (node (ref "CM4") (pin "119") (pinfunction "GND_119") (pintype "power_in"))
    )
    (net (code "143") (name "unconnected-(CM4O-EEPROM_nWP-Pad20)") (class "Default")
      (node (ref "CM4") (pin "20") (pinfunction "EEPROM_nWP_20") (pintype "passive+no_connect"))
    )
    (net (code "144") (name "unconnected-(CM4O-Reserved-Pad76)") (class "Default")
      (node (ref "CM4") (pin "76") (pinfunction "Reserved_76") (pintype "passive+no_connect"))
    )
    (net (code "145") (name "unconnected-(CM4O-Reserved-Pad104)") (class "Default")
      (node (ref "CM4") (pin "104") (pinfunction "Reserved_104") (pintype "passive+no_connect"))
    )
    (net (code "146") (name "unconnected-(CM4O-Reserved-Pad106)") (class "Default")
      (node (ref "CM4") (pin "106") (pinfunction "Reserved_106") (pintype "passive+no_connect"))
    )
    (net (code "147") (name "unconnected-(J14-Pad1)") (class "Default")
      (node (ref "J14") (pin "1") (pinfunction "1_1") (pintype "passive"))
    )
    (net (code "148") (name "unconnected-(J14-Pad2)") (class "Default")
      (node (ref "J14") (pin "2") (pinfunction "2_2") (pintype "passive"))
    )
    (net (code "149") (name "unconnected-(J14-Pad3)") (class "Default")
      (node (ref "J14") (pin "3") (pinfunction "3_3") (pintype "passive"))
    )
    (net (code "150") (name "unconnected-(J14-Pad4)") (class "Default")
      (node (ref "J14") (pin "4") (pinfunction "4_4") (pintype "passive"))
    )
    (net (code "151") (name "unconnected-(J14-Pad5)") (class "Default")
      (node (ref "J14") (pin "5") (pinfunction "5_5") (pintype "passive"))
    )
    (net (code "152") (name "unconnected-(J14-Pad6)") (class "Default")
      (node (ref "J14") (pin "6") (pinfunction "6_6") (pintype "passive"))
    )
    (net (code "153") (name "unconnected-(J14-Pad7)") (class "Default")
      (node (ref "J14") (pin "7") (pinfunction "7_7") (pintype "passive"))
    )
    (net (code "154") (name "unconnected-(J14-Pad8)") (class "Default")
      (node (ref "J14") (pin "8") (pinfunction "8_8") (pintype "passive"))
    )
    (net (code "155") (name "unconnected-(J14-Pad9)") (class "Default")
      (node (ref "J14") (pin "9") (pinfunction "9_9") (pintype "passive"))
    )
    (net (code "156") (name "unconnected-(J14-Pad10)") (class "Default")
      (node (ref "J14") (pin "10") (pinfunction "10_10") (pintype "passive"))
    )
    (net (code "157") (name "unconnected-(J14-Pad11)") (class "Default")
      (node (ref "J14") (pin "11") (pinfunction "11_11") (pintype "passive"))
    )
    (net (code "158") (name "unconnected-(J14-Pad12)") (class "Default")
      (node (ref "J14") (pin "12") (pinfunction "12_12") (pintype "passive"))
    )
    (net (code "159") (name "unconnected-(J14-Pad13)") (class "Default")
      (node (ref "J14") (pin "13") (pinfunction "13_13") (pintype "passive"))
    )
    (net (code "160") (name "unconnected-(J14-Pad14)") (class "Default")
      (node (ref "J14") (pin "14") (pinfunction "14_14") (pintype "passive"))
    )
    (net (code "161") (name "unconnected-(J14-Pad15)") (class "Default")
      (node (ref "J14") (pin "15") (pinfunction "15_15") (pintype "passive"))
    )
    (net (code "162") (name "unconnected-(J14-Pad16)") (class "Default")
      (node (ref "J14") (pin "16") (pinfunction "16_16") (pintype "passive"))
    )
    (net (code "163") (name "unconnected-(J14-Pad17)") (class "Default")
      (node (ref "J14") (pin "17") (pinfunction "17_17") (pintype "passive"))
    )
    (net (code "164") (name "unconnected-(J14-Pad18)") (class "Default")
      (node (ref "J14") (pin "18") (pinfunction "18_18") (pintype "passive"))
    )
    (net (code "165") (name "unconnected-(J14-Pad19)") (class "Default")
      (node (ref "J14") (pin "19") (pinfunction "19_19") (pintype "passive"))
    )
    (net (code "166") (name "unconnected-(J14-Pad20)") (class "Default")
      (node (ref "J14") (pin "20") (pinfunction "20_20") (pintype "passive"))
    )
    (net (code "167") (name "unconnected-(J14-Pad21)") (class "Default")
      (node (ref "J14") (pin "21") (pinfunction "21_21") (pintype "passive"))
    )
    (net (code "168") (name "unconnected-(J14-Pad22)") (class "Default")
      (node (ref "J14") (pin "22") (pinfunction "22_22") (pintype "passive"))
    )
    (net (code "169") (name "unconnected-(J14-Pad23)") (class "Default")
      (node (ref "J14") (pin "23") (pinfunction "23_23") (pintype "passive"))
    )
    (net (code "170") (name "unconnected-(J14-Pad24)") (class "Default")
      (node (ref "J14") (pin "24") (pinfunction "24_24") (pintype "passive"))
    )
    (net (code "171") (name "unconnected-(J14-Pad25)") (class "Default")
      (node (ref "J14") (pin "25") (pinfunction "25_25") (pintype "passive"))
    )
    (net (code "172") (name "unconnected-(J14-Pad26)") (class "Default")
      (node (ref "J14") (pin "26") (pinfunction "26_26") (pintype "passive"))
    )
    (net (code "173") (name "unconnected-(J14-Pad27)") (class "Default")
      (node (ref "J14") (pin "27") (pinfunction "27_27") (pintype "passive"))
    )
    (net (code "174") (name "unconnected-(J14-Pad28)") (class "Default")
      (node (ref "J14") (pin "28") (pinfunction "28_28") (pintype "passive"))
    )
    (net (code "175") (name "unconnected-(J14-Pad29)") (class "Default")
      (node (ref "J14") (pin "29") (pinfunction "29_29") (pintype "passive"))
    )
    (net (code "176") (name "unconnected-(J14-Pad30)") (class "Default")
      (node (ref "J14") (pin "30") (pinfunction "30_30") (pintype "passive"))
    )
    (net (code "177") (name "unconnected-(J14-Pad31)") (class "Default")
      (node (ref "J14") (pin "31") (pinfunction "31_31") (pintype "passive"))
    )
    (net (code "178") (name "unconnected-(J14-Pad32)") (class "Default")
      (node (ref "J14") (pin "32") (pinfunction "32_32") (pintype "passive"))
    )
    (net (code "179") (name "unconnected-(J14-Pad33)") (class "Default")
      (node (ref "J14") (pin "33") (pinfunction "33_33") (pintype "passive"))
    )
    (net (code "180") (name "unconnected-(J14-Pad34)") (class "Default")
      (node (ref "J14") (pin "34") (pinfunction "34_34") (pintype "passive"))
    )
    (net (code "181") (name "unconnected-(J14-Pad35)") (class "Default")
      (node (ref "J14") (pin "35") (pinfunction "35_35") (pintype "passive"))
    )
    (net (code "182") (name "unconnected-(J14-Pad36)") (class "Default")
      (node (ref "J14") (pin "36") (pinfunction "36_36") (pintype "passive"))
    )
    (net (code "183") (name "unconnected-(J14-Pad37)") (class "Default")
      (node (ref "J14") (pin "37") (pinfunction "37_37") (pintype "passive"))
    )
    (net (code "184") (name "unconnected-(J14-Pad38)") (class "Default")
      (node (ref "J14") (pin "38") (pinfunction "38_38") (pintype "passive"))
    )
    (net (code "185") (name "unconnected-(J14-Pad39)") (class "Default")
      (node (ref "J14") (pin "39") (pinfunction "39_39") (pintype "passive"))
    )
    (net (code "186") (name "unconnected-(J14-Pad40)") (class "Default")
      (node (ref "J14") (pin "40") (pinfunction "40_40") (pintype "passive"))
    )
    (net (code "187") (name "unconnected-(J14-Pad41)") (class "Default")
      (node (ref "J14") (pin "41") (pinfunction "41_41") (pintype "passive"))
    )
    (net (code "188") (name "unconnected-(J14-Pad42)") (class "Default")
      (node (ref "J14") (pin "42") (pinfunction "42_42") (pintype "passive"))
    )
    (net (code "189") (name "unconnected-(J14-Pad43)") (class "Default")
      (node (ref "J14") (pin "43") (pinfunction "43_43") (pintype "passive"))
    )
    (net (code "190") (name "unconnected-(J14-Pad44)") (class "Default")
      (node (ref "J14") (pin "44") (pinfunction "44_44") (pintype "passive"))
    )
    (net (code "191") (name "unconnected-(J14-Pad45)") (class "Default")
      (node (ref "J14") (pin "45") (pinfunction "45_45") (pintype "passive"))
    )
    (net (code "192") (name "unconnected-(J14-Pad46)") (class "Default")
      (node (ref "J14") (pin "46") (pinfunction "46_46") (pintype "passive"))
    )
    (net (code "193") (name "unconnected-(J14-Pad47)") (class "Default")
      (node (ref "J14") (pin "47") (pinfunction "47_47") (pintype "passive"))
    )
    (net (code "194") (name "unconnected-(J14-Pad48)") (class "Default")
      (node (ref "J14") (pin "48") (pinfunction "48_48") (pintype "passive"))
    )
    (net (code "195") (name "unconnected-(J14-Pad49)") (class "Default")
      (node (ref "J14") (pin "49") (pinfunction "49_49") (pintype "passive"))
    )
    (net (code "196") (name "unconnected-(J14-Pad50)") (class "Default")
      (node (ref "J14") (pin "50") (pinfunction "50_50") (pintype "passive"))
    )
    (net (code "197") (name "unconnected-(J14-Pad51)") (class "Default")
      (node (ref "J14") (pin "51") (pinfunction "51_51") (pintype "passive"))
    )
    (net (code "198") (name "unconnected-(J14-Pad52)") (class "Default")
      (node (ref "J14") (pin "52") (pinfunction "52_52") (pintype "passive"))
    )
    (net (code "199") (name "unconnected-(J14-Pad53)") (class "Default")
      (node (ref "J14") (pin "53") (pinfunction "53_53") (pintype "passive"))
    )
    (net (code "200") (name "unconnected-(J14-Pad54)") (class "Default")
      (node (ref "J14") (pin "54") (pinfunction "54_54") (pintype "passive"))
    )
    (net (code "201") (name "unconnected-(J14-Pad55)") (class "Default")
      (node (ref "J14") (pin "55") (pinfunction "55_55") (pintype "passive"))
    )
    (net (code "202") (name "unconnected-(J14-Pad56)") (class "Default")
      (node (ref "J14") (pin "56") (pinfunction "56_56") (pintype "passive"))
    )
    (net (code "203") (name "unconnected-(J14-Pad57)") (class "Default")
      (node (ref "J14") (pin "57") (pinfunction "57_57") (pintype "passive"))
    )
    (net (code "204") (name "unconnected-(J14-Pad58)") (class "Default")
      (node (ref "J14") (pin "58") (pinfunction "58_58") (pintype "passive"))
    )
    (net (code "205") (name "unconnected-(J14-Pad59)") (class "Default")
      (node (ref "J14") (pin "59") (pinfunction "59_59") (pintype "passive"))
    )
    (net (code "206") (name "unconnected-(J14-Pad60)") (class "Default")
      (node (ref "J14") (pin "60") (pinfunction "60_60") (pintype "passive"))
    )
    (net (code "207") (name "unconnected-(J14-Pad61)") (class "Default")
      (node (ref "J14") (pin "61") (pinfunction "61_61") (pintype "passive"))
    )
    (net (code "208") (name "unconnected-(J14-Pad62)") (class "Default")
      (node (ref "J14") (pin "62") (pinfunction "62_62") (pintype "passive"))
    )
    (net (code "209") (name "unconnected-(J14-Pad63)") (class "Default")
      (node (ref "J14") (pin "63") (pinfunction "63_63") (pintype "passive"))
    )
    (net (code "210") (name "unconnected-(J14-Pad64)") (class "Default")
      (node (ref "J14") (pin "64") (pinfunction "64_64") (pintype "passive"))
    )
    (net (code "211") (name "unconnected-(J14-Pad65)") (class "Default")
      (node (ref "J14") (pin "65") (pinfunction "65_65") (pintype "passive"))
    )
    (net (code "212") (name "unconnected-(J14-Pad66)") (class "Default")
      (node (ref "J14") (pin "66") (pinfunction "66_66") (pintype "passive"))
    )
    (net (code "213") (name "unconnected-(J14-Pad67)") (class "Default")
      (node (ref "J14") (pin "67") (pinfunction "67_67") (pintype "passive"))
    )
    (net (code "214") (name "unconnected-(J14-Pad68)") (class "Default")
      (node (ref "J14") (pin "68") (pinfunction "68_68") (pintype "passive"))
    )
    (net (code "215") (name "unconnected-(J14-Pad69)") (class "Default")
      (node (ref "J14") (pin "69") (pinfunction "69_69") (pintype "passive"))
    )
    (net (code "216") (name "unconnected-(J14-Pad70)") (class "Default")
      (node (ref "J14") (pin "70") (pinfunction "70_70") (pintype "passive"))
    )
    (net (code "217") (name "unconnected-(J14-Pad71)") (class "Default")
      (node (ref "J14") (pin "71") (pinfunction "71_71") (pintype "passive"))
    )
    (net (code "218") (name "unconnected-(J14-Pad72)") (class "Default")
      (node (ref "J14") (pin "72") (pinfunction "72_72") (pintype "passive"))
    )
    (net (code "219") (name "unconnected-(J14-Pad73)") (class "Default")
      (node (ref "J14") (pin "73") (pinfunction "73_73") (pintype "passive"))
    )
    (net (code "220") (name "unconnected-(J14-Pad74)") (class "Default")
      (node (ref "J14") (pin "74") (pinfunction "74_74") (pintype "passive"))
    )
    (net (code "221") (name "unconnected-(J14-Pad75)") (class "Default")
      (node (ref "J14") (pin "75") (pinfunction "75_75") (pintype "passive"))
    )
    (net (code "222") (name "unconnected-(J14-Pad76)") (class "Default")
      (node (ref "J14") (pin "76") (pinfunction "76_76") (pintype "passive"))
    )
    (net (code "223") (name "unconnected-(J14-Pad77)") (class "Default")
      (node (ref "J14") (pin "77") (pinfunction "77_77") (pintype "passive"))
    )
    (net (code "224") (name "unconnected-(J14-Pad78)") (class "Default")
      (node (ref "J14") (pin "78") (pinfunction "78_78") (pintype "passive"))
    )
    (net (code "225") (name "unconnected-(J14-Pad79)") (class "Default")
      (node (ref "J14") (pin "79") (pinfunction "79_79") (pintype "passive"))
    )
    (net (code "226") (name "unconnected-(J14-Pad80)") (class "Default")
      (node (ref "J14") (pin "80") (pinfunction "80_80") (pintype "passive"))
    )
    (net (code "227") (name "unconnected-(J14-Pad81)") (class "Default")
      (node (ref "J14") (pin "81") (pinfunction "81_81") (pintype "passive"))
    )
    (net (code "228") (name "unconnected-(J14-Pad82)") (class "Default")
      (node (ref "J14") (pin "82") (pinfunction "82_82") (pintype "passive"))
    )
    (net (code "229") (name "unconnected-(J14-Pad83)") (class "Default")
      (node (ref "J14") (pin "83") (pinfunction "83_83") (pintype "passive"))
    )
    (net (code "230") (name "unconnected-(J14-Pad84)") (class "Default")
      (node (ref "J14") (pin "84") (pinfunction "84_84") (pintype "passive"))
    )
    (net (code "231") (name "unconnected-(J14-Pad85)") (class "Default")
      (node (ref "J14") (pin "85") (pinfunction "85_85") (pintype "passive"))
    )
    (net (code "232") (name "unconnected-(J14-Pad86)") (class "Default")
      (node (ref "J14") (pin "86") (pinfunction "86_86") (pintype "passive"))
    )
    (net (code "233") (name "unconnected-(J14-Pad87)") (class "Default")
      (node (ref "J14") (pin "87") (pinfunction "87_87") (pintype "passive"))
    )
    (net (code "234") (name "unconnected-(J14-Pad88)") (class "Default")
      (node (ref "J14") (pin "88") (pinfunction "88_88") (pintype "passive"))
    )
    (net (code "235") (name "unconnected-(J14-Pad89)") (class "Default")
      (node (ref "J14") (pin "89") (pinfunction "89_89") (pintype "passive"))
    )
    (net (code "236") (name "unconnected-(J14-Pad90)") (class "Default")
      (node (ref "J14") (pin "90") (pinfunction "90_90") (pintype "passive"))
    )
    (net (code "237") (name "unconnected-(J14-Pad91)") (class "Default")
      (node (ref "J14") (pin "91") (pinfunction "91_91") (pintype "passive"))
    )
    (net (code "238") (name "unconnected-(J14-Pad92)") (class "Default")
      (node (ref "J14") (pin "92") (pinfunction "92_92") (pintype "passive"))
    )
    (net (code "239") (name "unconnected-(J14-Pad93)") (class "Default")
      (node (ref "J14") (pin "93") (pinfunction "93_93") (pintype "passive"))
    )
    (net (code "240") (name "unconnected-(J14-Pad94)") (class "Default")
      (node (ref "J14") (pin "94") (pinfunction "94_94") (pintype "passive"))
    )
    (net (code "241") (name "unconnected-(J14-Pad95)") (class "Default")
      (node (ref "J14") (pin "95") (pinfunction "95_95") (pintype "passive"))
    )
    (net (code "242") (name "unconnected-(J14-Pad96)") (class "Default")
      (node (ref "J14") (pin "96") (pinfunction "96_96") (pintype "passive"))
    )
    (net (code "243") (name "unconnected-(J14-Pad97)") (class "Default")
      (node (ref "J14") (pin "97") (pinfunction "97_97") (pintype "passive"))
    )
    (net (code "244") (name "unconnected-(J14-Pad98)") (class "Default")
      (node (ref "J14") (pin "98") (pinfunction "98_98") (pintype "passive"))
    )
    (net (code "245") (name "unconnected-(J14-Pad99)") (class "Default")
      (node (ref "J14") (pin "99") (pinfunction "99_99") (pintype "passive"))
    )
    (net (code "246") (name "unconnected-(J14-Pad100)") (class "Default")
      (node (ref "J14") (pin "100") (pinfunction "100_100") (pintype "passive"))
    )
    (net (code "247") (name "unconnected-(J15-Pad1)") (class "Default")
      (node (ref "J15") (pin "1") (pinfunction "1_1") (pintype "passive"))
    )
    (net (code "248") (name "unconnected-(J15-Pad2)") (class "Default")
      (node (ref "J15") (pin "2") (pinfunction "2_2") (pintype "passive"))
    )
    (net (code "249") (name "unconnected-(J15-Pad3)") (class "Default")
      (node (ref "J15") (pin "3") (pinfunction "3_3") (pintype "passive"))
    )
    (net (code "250") (name "unconnected-(J15-Pad4)") (class "Default")
      (node (ref "J15") (pin "4") (pinfunction "4_4") (pintype "passive"))
    )
    (net (code "251") (name "unconnected-(J15-Pad5)") (class "Default")
      (node (ref "J15") (pin "5") (pinfunction "5_5") (pintype "passive"))
    )
    (net (code "252") (name "unconnected-(J15-Pad6)") (class "Default")
      (node (ref "J15") (pin "6") (pinfunction "6_6") (pintype "passive"))
    )
    (net (code "253") (name "unconnected-(J15-Pad7)") (class "Default")
      (node (ref "J15") (pin "7") (pinfunction "7_7") (pintype "passive"))
    )
    (net (code "254") (name "unconnected-(J15-Pad8)") (class "Default")
      (node (ref "J15") (pin "8") (pinfunction "8_8") (pintype "passive"))
    )
    (net (code "255") (name "unconnected-(J15-Pad9)") (class "Default")
      (node (ref "J15") (pin "9") (pinfunction "9_9") (pintype "passive"))
    )
    (net (code "256") (name "unconnected-(J15-Pad10)") (class "Default")
      (node (ref "J15") (pin "10") (pinfunction "10_10") (pintype "passive"))
    )
    (net (code "257") (name "unconnected-(J15-Pad11)") (class "Default")
      (node (ref "J15") (pin "11") (pinfunction "11_11") (pintype "passive"))
    )
    (net (code "258") (name "unconnected-(J15-Pad12)") (class "Default")
      (node (ref "J15") (pin "12") (pinfunction "12_12") (pintype "passive"))
    )
    (net (code "259") (name "unconnected-(J15-Pad13)") (class "Default")
      (node (ref "J15") (pin "13") (pinfunction "13_13") (pintype "passive"))
    )
    (net (code "260") (name "unconnected-(J15-Pad14)") (class "Default")
      (node (ref "J15") (pin "14") (pinfunction "14_14") (pintype "passive"))
    )
    (net (code "261") (name "unconnected-(J15-Pad15)") (class "Default")
      (node (ref "J15") (pin "15") (pinfunction "15_15") (pintype "passive"))
    )
    (net (code "262") (name "unconnected-(J15-Pad16)") (class "Default")
      (node (ref "J15") (pin "16") (pinfunction "16_16") (pintype "passive"))
    )
    (net (code "263") (name "unconnected-(J15-Pad17)") (class "Default")
      (node (ref "J15") (pin "17") (pinfunction "17_17") (pintype "passive"))
    )
    (net (code "264") (name "unconnected-(J15-Pad18)") (class "Default")
      (node (ref "J15") (pin "18") (pinfunction "18_18") (pintype "passive"))
    )
    (net (code "265") (name "unconnected-(J15-Pad19)") (class "Default")
      (node (ref "J15") (pin "19") (pinfunction "19_19") (pintype "passive"))
    )
    (net (code "266") (name "unconnected-(J15-Pad20)") (class "Default")
      (node (ref "J15") (pin "20") (pinfunction "20_20") (pintype "passive"))
    )
    (net (code "267") (name "unconnected-(J15-Pad21)") (class "Default")
      (node (ref "J15") (pin "21") (pinfunction "21_21") (pintype "passive"))
    )
    (net (code "268") (name "unconnected-(J15-Pad22)") (class "Default")
      (node (ref "J15") (pin "22") (pinfunction "22_22") (pintype "passive"))
    )
    (net (code "269") (name "unconnected-(J15-Pad23)") (class "Default")
      (node (ref "J15") (pin "23") (pinfunction "23_23") (pintype "passive"))
    )
    (net (code "270") (name "unconnected-(J15-Pad24)") (class "Default")
      (node (ref "J15") (pin "24") (pinfunction "24_24") (pintype "passive"))
    )
    (net (code "271") (name "unconnected-(J15-Pad25)") (class "Default")
      (node (ref "J15") (pin "25") (pinfunction "25_25") (pintype "passive"))
    )
    (net (code "272") (name "unconnected-(J15-Pad26)") (class "Default")
      (node (ref "J15") (pin "26") (pinfunction "26_26") (pintype "passive"))
    )
    (net (code "273") (name "unconnected-(J15-Pad27)") (class "Default")
      (node (ref "J15") (pin "27") (pinfunction "27_27") (pintype "passive"))
    )
    (net (code "274") (name "unconnected-(J15-Pad28)") (class "Default")
      (node (ref "J15") (pin "28") (pinfunction "28_28") (pintype "passive"))
    )
    (net (code "275") (name "unconnected-(J15-Pad29)") (class "Default")
      (node (ref "J15") (pin "29") (pinfunction "29_29") (pintype "passive"))
    )
    (net (code "276") (name "unconnected-(J15-Pad30)") (class "Default")
      (node (ref "J15") (pin "30") (pinfunction "30_30") (pintype "passive"))
    )
    (net (code "277") (name "unconnected-(J15-Pad31)") (class "Default")
      (node (ref "J15") (pin "31") (pinfunction "31_31") (pintype "passive"))
    )
    (net (code "278") (name "unconnected-(J15-Pad32)") (class "Default")
      (node (ref "J15") (pin "32") (pinfunction "32_32") (pintype "passive"))
    )
    (net (code "279") (name "unconnected-(J15-Pad33)") (class "Default")
      (node (ref "J15") (pin "33") (pinfunction "33_33") (pintype "passive"))
    )
    (net (code "280") (name "unconnected-(J15-Pad34)") (class "Default")
      (node (ref "J15") (pin "34") (pinfunction "34_34") (pintype "passive"))
    )
    (net (code "281") (name "unconnected-(J15-Pad35)") (class "Default")
      (node (ref "J15") (pin "35") (pinfunction "35_35") (pintype "passive"))
    )
    (net (code "282") (name "unconnected-(J15-Pad36)") (class "Default")
      (node (ref "J15") (pin "36") (pinfunction "36_36") (pintype "passive"))
    )
    (net (code "283") (name "unconnected-(J15-Pad37)") (class "Default")
      (node (ref "J15") (pin "37") (pinfunction "37_37") (pintype "passive"))
    )
    (net (code "284") (name "unconnected-(J15-Pad38)") (class "Default")
      (node (ref "J15") (pin "38") (pinfunction "38_38") (pintype "passive"))
    )
    (net (code "285") (name "unconnected-(J15-Pad39)") (class "Default")
      (node (ref "J15") (pin "39") (pinfunction "39_39") (pintype "passive"))
    )
    (net (code "286") (name "unconnected-(J15-Pad40)") (class "Default")
      (node (ref "J15") (pin "40") (pinfunction "40_40") (pintype "passive"))
    )
    (net (code "287") (name "unconnected-(J15-Pad41)") (class "Default")
      (node (ref "J15") (pin "41") (pinfunction "41_41") (pintype "passive"))
    )
    (net (code "288") (name "unconnected-(J15-Pad42)") (class "Default")
      (node (ref "J15") (pin "42") (pinfunction "42_42") (pintype "passive"))
    )
    (net (code "289") (name "unconnected-(J15-Pad43)") (class "Default")
      (node (ref "J15") (pin "43") (pinfunction "43_43") (pintype "passive"))
    )
    (net (code "290") (name "unconnected-(J15-Pad44)") (class "Default")
      (node (ref "J15") (pin "44") (pinfunction "44_44") (pintype "passive"))
    )
    (net (code "291") (name "unconnected-(J15-Pad45)") (class "Default")
      (node (ref "J15") (pin "45") (pinfunction "45_45") (pintype "passive"))
    )
    (net (code "292") (name "unconnected-(J15-Pad46)") (class "Default")
      (node (ref "J15") (pin "46") (pinfunction "46_46") (pintype "passive"))
    )
    (net (code "293") (name "unconnected-(J15-Pad47)") (class "Default")
      (node (ref "J15") (pin "47") (pinfunction "47_47") (pintype "passive"))
    )
    (net (code "294") (name "unconnected-(J15-Pad48)") (class "Default")
      (node (ref "J15") (pin "48") (pinfunction "48_48") (pintype "passive"))
    )
    (net (code "295") (name "unconnected-(J15-Pad49)") (class "Default")
      (node (ref "J15") (pin "49") (pinfunction "49_49") (pintype "passive"))
    )
    (net (code "296") (name "unconnected-(J15-Pad50)") (class "Default")
      (node (ref "J15") (pin "50") (pinfunction "50_50") (pintype "passive"))
    )
    (net (code "297") (name "unconnected-(J15-Pad51)") (class "Default")
      (node (ref "J15") (pin "51") (pinfunction "51_51") (pintype "passive"))
    )
    (net (code "298") (name "unconnected-(J15-Pad52)") (class "Default")
      (node (ref "J15") (pin "52") (pinfunction "52_52") (pintype "passive"))
    )
    (net (code "299") (name "unconnected-(J15-Pad53)") (class "Default")
      (node (ref "J15") (pin "53") (pinfunction "53_53") (pintype "passive"))
    )
    (net (code "300") (name "unconnected-(J15-Pad54)") (class "Default")
      (node (ref "J15") (pin "54") (pinfunction "54_54") (pintype "passive"))
    )
    (net (code "301") (name "unconnected-(J15-Pad55)") (class "Default")
      (node (ref "J15") (pin "55") (pinfunction "55_55") (pintype "passive"))
    )
    (net (code "302") (name "unconnected-(J15-Pad56)") (class "Default")
      (node (ref "J15") (pin "56") (pinfunction "56_56") (pintype "passive"))
    )
    (net (code "303") (name "unconnected-(J15-Pad57)") (class "Default")
      (node (ref "J15") (pin "57") (pinfunction "57_57") (pintype "passive"))
    )
    (net (code "304") (name "unconnected-(J15-Pad58)") (class "Default")
      (node (ref "J15") (pin "58") (pinfunction "58_58") (pintype "passive"))
    )
    (net (code "305") (name "unconnected-(J15-Pad59)") (class "Default")
      (node (ref "J15") (pin "59") (pinfunction "59_59") (pintype "passive"))
    )
    (net (code "306") (name "unconnected-(J15-Pad60)") (class "Default")
      (node (ref "J15") (pin "60") (pinfunction "60_60") (pintype "passive"))
    )
    (net (code "307") (name "unconnected-(J15-Pad61)") (class "Default")
      (node (ref "J15") (pin "61") (pinfunction "61_61") (pintype "passive"))
    )
    (net (code "308") (name "unconnected-(J15-Pad62)") (class "Default")
      (node (ref "J15") (pin "62") (pinfunction "62_62") (pintype "passive"))
    )
    (net (code "309") (name "unconnected-(J15-Pad63)") (class "Default")
      (node (ref "J15") (pin "63") (pinfunction "63_63") (pintype "passive"))
    )
    (net (code "310") (name "unconnected-(J15-Pad64)") (class "Default")
      (node (ref "J15") (pin "64") (pinfunction "64_64") (pintype "passive"))
    )
    (net (code "311") (name "unconnected-(J15-Pad65)") (class "Default")
      (node (ref "J15") (pin "65") (pinfunction "65_65") (pintype "passive"))
    )
    (net (code "312") (name "unconnected-(J15-Pad66)") (class "Default")
      (node (ref "J15") (pin "66") (pinfunction "66_66") (pintype "passive"))
    )
    (net (code "313") (name "unconnected-(J15-Pad67)") (class "Default")
      (node (ref "J15") (pin "67") (pinfunction "67_67") (pintype "passive"))
    )
    (net (code "314") (name "unconnected-(J15-Pad68)") (class "Default")
      (node (ref "J15") (pin "68") (pinfunction "68_68") (pintype "passive"))
    )
    (net (code "315") (name "unconnected-(J15-Pad69)") (class "Default")
      (node (ref "J15") (pin "69") (pinfunction "69_69") (pintype "passive"))
    )
    (net (code "316") (name "unconnected-(J15-Pad70)") (class "Default")
      (node (ref "J15") (pin "70") (pinfunction "70_70") (pintype "passive"))
    )
    (net (code "317") (name "unconnected-(J15-Pad71)") (class "Default")
      (node (ref "J15") (pin "71") (pinfunction "71_71") (pintype "passive"))
    )
    (net (code "318") (name "unconnected-(J15-Pad72)") (class "Default")
      (node (ref "J15") (pin "72") (pinfunction "72_72") (pintype "passive"))
    )
    (net (code "319") (name "unconnected-(J15-Pad73)") (class "Default")
      (node (ref "J15") (pin "73") (pinfunction "73_73") (pintype "passive"))
    )
    (net (code "320") (name "unconnected-(J15-Pad74)") (class "Default")
      (node (ref "J15") (pin "74") (pinfunction "74_74") (pintype "passive"))
    )
    (net (code "321") (name "unconnected-(J15-Pad75)") (class "Default")
      (node (ref "J15") (pin "75") (pinfunction "75_75") (pintype "passive"))
    )
    (net (code "322") (name "unconnected-(J15-Pad76)") (class "Default")
      (node (ref "J15") (pin "76") (pinfunction "76_76") (pintype "passive"))
    )
    (net (code "323") (name "unconnected-(J15-Pad77)") (class "Default")
      (node (ref "J15") (pin "77") (pinfunction "77_77") (pintype "passive"))
    )
    (net (code "324") (name "unconnected-(J15-Pad78)") (class "Default")
      (node (ref "J15") (pin "78") (pinfunction "78_78") (pintype "passive"))
    )
    (net (code "325") (name "unconnected-(J15-Pad79)") (class "Default")
      (node (ref "J15") (pin "79") (pinfunction "79_79") (pintype "passive"))
    )
    (net (code "326") (name "unconnected-(J15-Pad80)") (class "Default")
      (node (ref "J15") (pin "80") (pinfunction "80_80") (pintype "passive"))
    )
    (net (code "327") (name "unconnected-(J15-Pad81)") (class "Default")
      (node (ref "J15") (pin "81") (pinfunction "81_81") (pintype "passive"))
    )
    (net (code "328") (name "unconnected-(J15-Pad82)") (class "Default")
      (node (ref "J15") (pin "82") (pinfunction "82_82") (pintype "passive"))
    )
    (net (code "329") (name "unconnected-(J15-Pad83)") (class "Default")
      (node (ref "J15") (pin "83") (pinfunction "83_83") (pintype "passive"))
    )
    (net (code "330") (name "unconnected-(J15-Pad84)") (class "Default")
      (node (ref "J15") (pin "84") (pinfunction "84_84") (pintype "passive"))
    )
    (net (code "331") (name "unconnected-(J15-Pad85)") (class "Default")
      (node (ref "J15") (pin "85") (pinfunction "85_85") (pintype "passive"))
    )
    (net (code "332") (name "unconnected-(J15-Pad86)") (class "Default")
      (node (ref "J15") (pin "86") (pinfunction "86_86") (pintype "passive"))
    )
    (net (code "333") (name "unconnected-(J15-Pad87)") (class "Default")
      (node (ref "J15") (pin "87") (pinfunction "87_87") (pintype "passive"))
    )
    (net (code "334") (name "unconnected-(J15-Pad88)") (class "Default")
      (node (ref "J15") (pin "88") (pinfunction "88_88") (pintype "passive"))
    )
    (net (code "335") (name "unconnected-(J15-Pad89)") (class "Default")
      (node (ref "J15") (pin "89") (pinfunction "89_89") (pintype "passive"))
    )
    (net (code "336") (name "unconnected-(J15-Pad90)") (class "Default")
      (node (ref "J15") (pin "90") (pinfunction "90_90") (pintype "passive"))
    )
    (net (code "337") (name "unconnected-(J15-Pad91)") (class "Default")
      (node (ref "J15") (pin "91") (pinfunction "91_91") (pintype "passive"))
    )
    (net (code "338") (name "unconnected-(J15-Pad92)") (class "Default")
      (node (ref "J15") (pin "92") (pinfunction "92_92") (pintype "passive"))
    )
    (net (code "339") (name "unconnected-(J15-Pad93)") (class "Default")
      (node (ref "J15") (pin "93") (pinfunction "93_93") (pintype "passive"))
    )
    (net (code "340") (name "unconnected-(J15-Pad94)") (class "Default")
      (node (ref "J15") (pin "94") (pinfunction "94_94") (pintype "passive"))
    )
    (net (code "341") (name "unconnected-(J15-Pad95)") (class "Default")
      (node (ref "J15") (pin "95") (pinfunction "95_95") (pintype "passive"))
    )
    (net (code "342") (name "unconnected-(J15-Pad96)") (class "Default")
      (node (ref "J15") (pin "96") (pinfunction "96_96") (pintype "passive"))
    )
    (net (code "343") (name "unconnected-(J15-Pad97)") (class "Default")
      (node (ref "J15") (pin "97") (pinfunction "97_97") (pintype "passive"))
    )
    (net (code "344") (name "unconnected-(J15-Pad98)") (class "Default")
      (node (ref "J15") (pin "98") (pinfunction "98_98") (pintype "passive"))
    )
    (net (code "345") (name "unconnected-(J15-Pad99)") (class "Default")
      (node (ref "J15") (pin "99") (pinfunction "99_99") (pintype "passive"))
    )
    (net (code "346") (name "unconnected-(J15-Pad100)") (class "Default")
      (node (ref "J15") (pin "100") (pinfunction "100_100") (pintype "passive"))
    )
  )
)
